# SCH_hEART-led_2026-05-04.net
KiCad netlist of a schematic drawn in EasyEDA
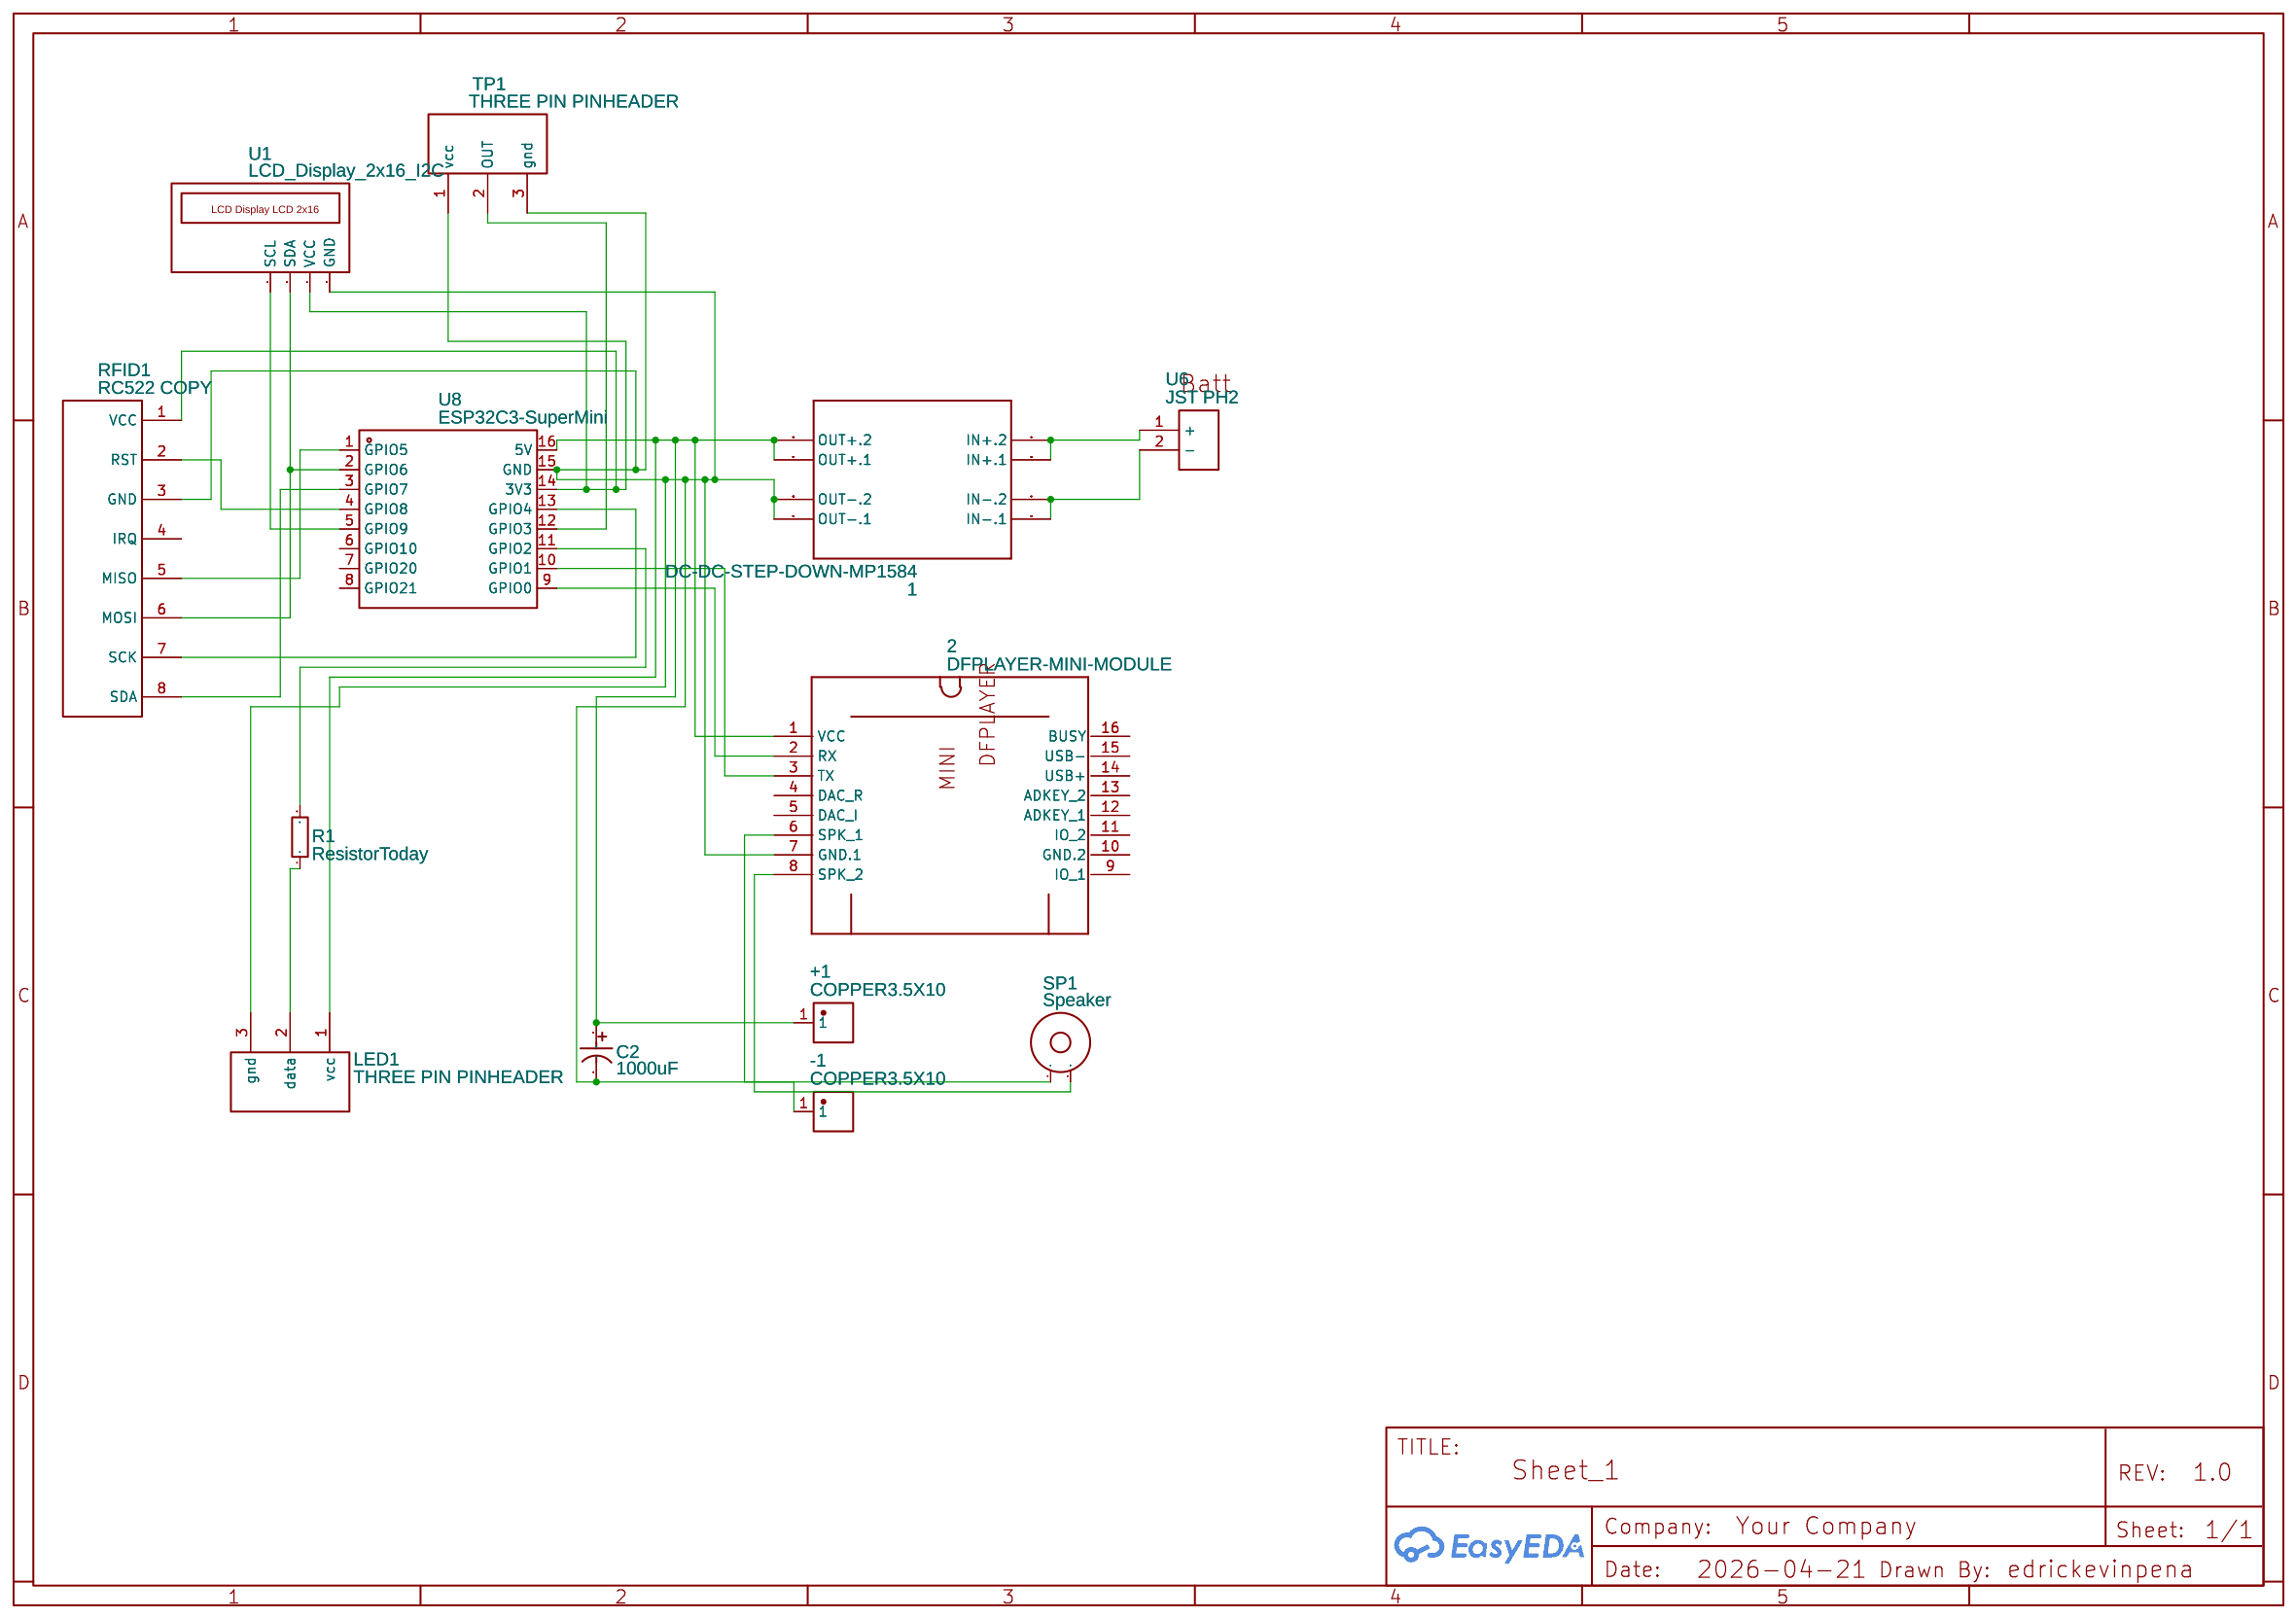
[diagram p0: schematic sheet]

(export (version "E")
  (design (tool "Eeschema 10.0.6"))
  (components
    (comp (ref "+1") (value "COPPER3.5X10") (libsource (lib "") (part "COPPER3.5X10_1")))
    (comp (ref "-1") (value "COPPER3.5X10") (libsource (lib "") (part "COPPER3.5X10")))
    (comp (ref "1") (value "DC-DC-STEP-DOWN-MP1584") (libsource (lib "") (part "DC-DC-STEP-DOWN-MP1584")))
    (comp (ref "2") (value "DFPLAYER-MINI-MODULE") (libsource (lib "") (part "DFPLAYER-MINI-MODULE")))
    (comp (ref "C2")
      (value "1000uF")
      (fields
        (field (name "Manufacturer Part") "KM108M050J25RR0VH2FP0")
        (field (name "Manufacturer") "CX(承兴)")
      )
      (libsource (lib "") (part "1000UF 50V"))
    )
    (comp (ref "LED1") (value "THREE PIN PINHEADER") (libsource (lib "") (part "THREE PIN PINHEADER")))
    (comp (ref "R1")
      (value "ResistorToday")
      (fields (field (name "Manufacturer Part") "EWWR0001J20R0T9"))
      (libsource (lib "") (part "RESISTOR NORMAL COPY"))
    )
    (comp (ref "RFID1") (value "RC522 COPY") (libsource (lib "") (part "RC522 COPY")))
    (comp (ref "SP1") (value "Speaker") (libsource (lib "") (part "Speaker")))
    (comp (ref "TP1") (value "THREE PIN PINHEADER") (libsource (lib "") (part "THREE PIN PINHEADER_1")))
    (comp (ref "U1") (value "LCD_Display_2x16_I2C") (libsource (lib "") (part "LCD_Display_2x16_I2C")))
    (comp (ref "U6") (value "JST PH2") (libsource (lib "") (part "JST PH2")))
    (comp (ref "U8") (value "ESP32C3-SuperMini") (libsource (lib "") (part "ESP32C3-SuperMini")))
  )
  (nets
    (net (code "1") (name "Net-(2-GND.1)") (class "Default")
      (node (ref "-1") (pin "1") (pinfunction "1_1") (pintype "unspecified"))
      (node (ref "1") (pin "OUT-.1") (pinfunction "OUT-.1_OUT-.1") (pintype "bidirectional"))
      (node (ref "1") (pin "OUT-.2") (pinfunction "OUT-.2_OUT-.2") (pintype "bidirectional"))
      (node (ref "2") (pin "7") (pinfunction "GND.1_7") (pintype "bidirectional"))
      (node (ref "C2") (pin "2") (pinfunction "2_2") (pintype "input"))
      (node (ref "LED1") (pin "3") (pinfunction "gnd_3") (pintype "unspecified"))
      (node (ref "RFID1") (pin "3") (pinfunction "GND_3") (pintype "unspecified"))
      (node (ref "TP1") (pin "3") (pinfunction "gnd_3") (pintype "unspecified"))
      (node (ref "U1") (pin "1") (pinfunction "GND_1") (pintype "unspecified"))
      (node (ref "U8") (pin "15") (pinfunction "GND_15") (pintype "unspecified"))
    )
    (net (code "2") (name "Net-(2-RX)") (class "Default")
      (node (ref "2") (pin "2") (pinfunction "RX_2") (pintype "bidirectional"))
      (node (ref "U8") (pin "9") (pinfunction "GPIO0_9") (pintype "unspecified"))
    )
    (net (code "3") (name "Net-(2-SPK_1)") (class "Default")
      (node (ref "2") (pin "6") (pinfunction "SPK_1_6") (pintype "bidirectional"))
      (node (ref "SP1") (pin "1") (pinfunction "1_1") (pintype "unspecified"))
    )
    (net (code "4") (name "Net-(2-SPK_2)") (class "Default")
      (node (ref "2") (pin "8") (pinfunction "SPK_2_8") (pintype "bidirectional"))
      (node (ref "SP1") (pin "2") (pinfunction "2_2") (pintype "unspecified"))
    )
    (net (code "5") (name "Net-(2-TX)") (class "Default")
      (node (ref "2") (pin "3") (pinfunction "TX_3") (pintype "bidirectional"))
      (node (ref "U8") (pin "10") (pinfunction "GPIO1_10") (pintype "unspecified"))
    )
    (net (code "6") (name "Net-(2-VCC)") (class "Default")
      (node (ref "+1") (pin "1") (pinfunction "1_1") (pintype "unspecified"))
      (node (ref "1") (pin "OUT+.1") (pinfunction "OUT+.1_OUT+.1") (pintype "bidirectional"))
      (node (ref "1") (pin "OUT+.2") (pinfunction "OUT+.2_OUT+.2") (pintype "bidirectional"))
      (node (ref "2") (pin "1") (pinfunction "VCC_1") (pintype "bidirectional"))
      (node (ref "C2") (pin "1") (pinfunction "1_1") (pintype "input"))
      (node (ref "LED1") (pin "1") (pinfunction "vcc_1") (pintype "unspecified"))
      (node (ref "U8") (pin "16") (pinfunction "5V_16") (pintype "unspecified"))
    )
    (net (code "7") (name "Net-(LED1-data)") (class "Default")
      (node (ref "LED1") (pin "2") (pinfunction "data_2") (pintype "unspecified"))
      (node (ref "R1") (pin "1") (pinfunction "1_1") (pintype "unspecified"))
    )
    (net (code "8") (name "Net-(RFID1-MISO)") (class "Default")
      (node (ref "RFID1") (pin "5") (pinfunction "MISO_5") (pintype "unspecified"))
      (node (ref "U8") (pin "1") (pinfunction "GPIO5_1") (pintype "unspecified"))
    )
    (net (code "9") (name "Net-(RFID1-MOSI)") (class "Default")
      (node (ref "RFID1") (pin "6") (pinfunction "MOSI_6") (pintype "unspecified"))
      (node (ref "U1") (pin "3") (pinfunction "SDA_3") (pintype "unspecified"))
      (node (ref "U8") (pin "2") (pinfunction "GPIO6_2") (pintype "unspecified"))
    )
    (net (code "10") (name "Net-(RFID1-RST)") (class "Default")
      (node (ref "RFID1") (pin "2") (pinfunction "RST_2") (pintype "unspecified"))
      (node (ref "U8") (pin "4") (pinfunction "GPIO8_4") (pintype "unspecified"))
    )
    (net (code "11") (name "Net-(RFID1-SCK)") (class "Default")
      (node (ref "RFID1") (pin "7") (pinfunction "SCK_7") (pintype "unspecified"))
      (node (ref "U8") (pin "13") (pinfunction "GPIO4_13") (pintype "unspecified"))
    )
    (net (code "12") (name "Net-(RFID1-SDA)") (class "Default")
      (node (ref "RFID1") (pin "8") (pinfunction "SDA_8") (pintype "unspecified"))
      (node (ref "U8") (pin "3") (pinfunction "GPIO7_3") (pintype "unspecified"))
    )
    (net (code "13") (name "Net-(RFID1-VCC)") (class "Default")
      (node (ref "RFID1") (pin "1") (pinfunction "VCC_1") (pintype "unspecified"))
      (node (ref "TP1") (pin "1") (pinfunction "vcc_1") (pintype "unspecified"))
      (node (ref "U1") (pin "2") (pinfunction "VCC_2") (pintype "unspecified"))
      (node (ref "U8") (pin "14") (pinfunction "3V3_14") (pintype "unspecified"))
    )
    (net (code "14") (name "Net-(TP1-OUT)") (class "Default")
      (node (ref "TP1") (pin "2") (pinfunction "OUT_2") (pintype "unspecified"))
      (node (ref "U8") (pin "12") (pinfunction "GPIO3_12") (pintype "unspecified"))
    )
    (net (code "15") (name "Net-(U1-SCL)") (class "Default")
      (node (ref "U1") (pin "4") (pinfunction "SCL_4") (pintype "unspecified"))
      (node (ref "U8") (pin "5") (pinfunction "GPIO9_5") (pintype "unspecified"))
    )
    (net (code "16") (name "Net-(U6-+)") (class "Default")
      (node (ref "1") (pin "IN+.1") (pinfunction "IN+.1_IN+.1") (pintype "bidirectional"))
      (node (ref "1") (pin "IN+.2") (pinfunction "IN+.2_IN+.2") (pintype "bidirectional"))
      (node (ref "U6") (pin "1") (pinfunction "+_1") (pintype "unspecified"))
    )
    (net (code "17") (name "Net-(U6--)") (class "Default")
      (node (ref "1") (pin "IN-.1") (pinfunction "IN-.1_IN-.1") (pintype "bidirectional"))
      (node (ref "1") (pin "IN-.2") (pinfunction "IN-.2_IN-.2") (pintype "bidirectional"))
      (node (ref "U6") (pin "2") (pinfunction "-_2") (pintype "unspecified"))
    )
    (net (code "18") (name "Net-(U8-GPIO2)") (class "Default")
      (node (ref "R1") (pin "2") (pinfunction "2_2") (pintype "unspecified"))
      (node (ref "U8") (pin "11") (pinfunction "GPIO2_11") (pintype "unspecified"))
    )
    (net (code "19") (name "unconnected-(2-ADKEY_1-Pad12)") (class "Default")
      (node (ref "2") (pin "12") (pinfunction "ADKEY_1_12") (pintype "bidirectional"))
    )
    (net (code "20") (name "unconnected-(2-ADKEY_2-Pad13)") (class "Default")
      (node (ref "2") (pin "13") (pinfunction "ADKEY_2_13") (pintype "bidirectional"))
    )
    (net (code "21") (name "unconnected-(2-BUSY-Pad16)") (class "Default")
      (node (ref "2") (pin "16") (pinfunction "BUSY_16") (pintype "bidirectional"))
    )
    (net (code "22") (name "unconnected-(2-DAC_I-Pad5)") (class "Default")
      (node (ref "2") (pin "5") (pinfunction "DAC_I_5") (pintype "bidirectional"))
    )
    (net (code "23") (name "unconnected-(2-DAC_R-Pad4)") (class "Default")
      (node (ref "2") (pin "4") (pinfunction "DAC_R_4") (pintype "bidirectional"))
    )
    (net (code "24") (name "unconnected-(2-GND.2-Pad10)") (class "Default")
      (node (ref "2") (pin "10") (pinfunction "GND.2_10") (pintype "bidirectional"))
    )
    (net (code "25") (name "unconnected-(2-IO_1-Pad9)") (class "Default")
      (node (ref "2") (pin "9") (pinfunction "IO_1_9") (pintype "bidirectional"))
    )
    (net (code "26") (name "unconnected-(2-IO_2-Pad11)") (class "Default")
      (node (ref "2") (pin "11") (pinfunction "IO_2_11") (pintype "bidirectional"))
    )
    (net (code "27") (name "unconnected-(2-USB+-Pad14)") (class "Default")
      (node (ref "2") (pin "14") (pinfunction "USB+_14") (pintype "bidirectional"))
    )
    (net (code "28") (name "unconnected-(2-USB--Pad15)") (class "Default")
      (node (ref "2") (pin "15") (pinfunction "USB-_15") (pintype "bidirectional"))
    )
    (net (code "29") (name "unconnected-(RFID1-IRQ-Pad4)") (class "Default")
      (node (ref "RFID1") (pin "4") (pinfunction "IRQ_4") (pintype "unspecified"))
    )
    (net (code "30") (name "unconnected-(U8-GPIO10-Pad6)") (class "Default")
      (node (ref "U8") (pin "6") (pinfunction "GPIO10_6") (pintype "unspecified"))
    )
    (net (code "31") (name "unconnected-(U8-GPIO20-Pad7)") (class "Default")
      (node (ref "U8") (pin "7") (pinfunction "GPIO20_7") (pintype "unspecified"))
    )
    (net (code "32") (name "unconnected-(U8-GPIO21-Pad8)") (class "Default")
      (node (ref "U8") (pin "8") (pinfunction "GPIO21_8") (pintype "unspecified"))
    )
  )
)
